# CrabTimerMain.net
KiCad netlist of a schematic drawn in EAGLE
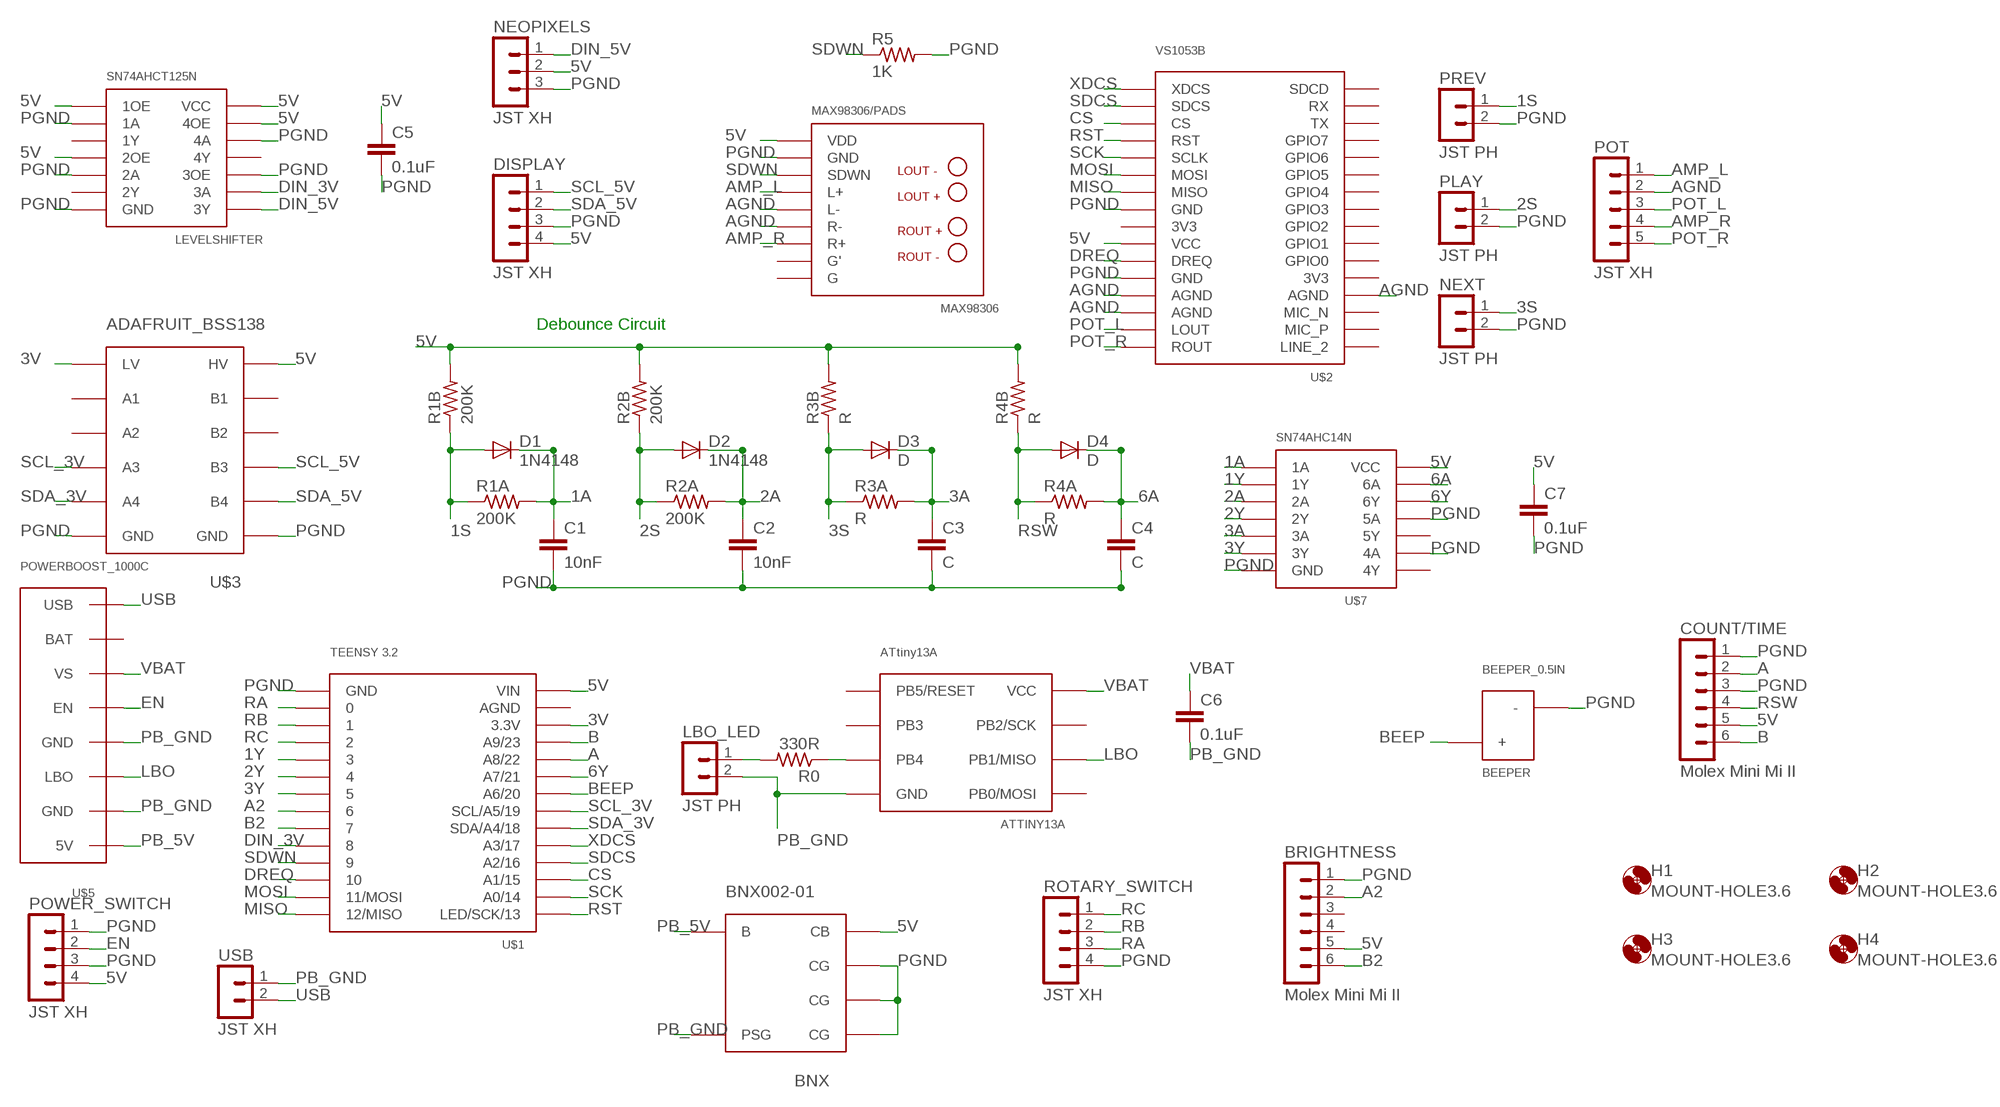
[diagram p0: schematic, sheet 1]

(export (version "E")
  (design (tool "Eeschema 10.0.6"))
  (components
    (comp (ref "ATTINY13A")
      (value "ATtiny13A")
      (footprint "eagle-import:ATTINY13A")
      (libsource (lib "eagle-import") (part "ATTINY13A"))
    )
    (comp (ref "BEEPER")
      (value "BEEPER_0.5IN")
      (footprint "eagle-import:BEEPER_0.5IN")
      (libsource (lib "eagle-import") (part "BEEPER_0.5IN"))
    )
    (comp (ref "BNX002-01")
      (value "BNX")
      (footprint "eagle-import:BNX002-01")
      (libsource (lib "eagle-import") (part "BNX"))
    )
    (comp (ref "BRIGHTNESS")
      (value "Molex Mini Mi II")
      (footprint "eagle-import:55447-0670")
      (libsource (lib "eagle-import") (part "MOLEX-55447-0670LONG_PADS"))
    )
    (comp (ref "C1")
      (value "10nF")
      (footprint "eagle-import:CAPACITOR_0.1IN")
      (libsource (lib "eagle-import") (part "CAPACITORS0.1IN"))
    )
    (comp (ref "C2")
      (value "10nF")
      (footprint "eagle-import:CAPACITOR_0.1IN")
      (libsource (lib "eagle-import") (part "CAPACITORS0.1IN"))
    )
    (comp (ref "C3")
      (value "C")
      (footprint "eagle-import:CAPACITOR_0.1IN")
      (libsource (lib "eagle-import") (part "CAPACITORS0.1IN"))
    )
    (comp (ref "C4")
      (value "C")
      (footprint "eagle-import:CAPACITOR_0.1IN")
      (libsource (lib "eagle-import") (part "CAPACITORS0.1IN"))
    )
    (comp (ref "C5")
      (value "0.1uF")
      (footprint "eagle-import:CAPACITOR_0.1IN")
      (libsource (lib "eagle-import") (part "CAPACITORS0.1IN"))
    )
    (comp (ref "C6")
      (value "0.1uF")
      (footprint "eagle-import:CAPACITOR_0.1IN")
      (libsource (lib "eagle-import") (part "CAPACITORS0.1IN"))
    )
    (comp (ref "C7")
      (value "0.1uF")
      (footprint "eagle-import:CAPACITOR_0.1IN")
      (libsource (lib "eagle-import") (part "CAPACITORS0.1IN"))
    )
    (comp (ref "COUNT/TIME")
      (value "Molex Mini Mi II")
      (footprint "eagle-import:55454-0670")
      (libsource (lib "eagle-import") (part "MOLEX-55454-0670LONGPADS"))
    )
    (comp (ref "D1")
      (value "1N4148")
      (footprint "eagle-import:1N4148")
      (libsource (lib "eagle-import") (part "1N4148"))
    )
    (comp (ref "D2")
      (value "1N4148")
      (footprint "eagle-import:1N4148")
      (libsource (lib "eagle-import") (part "1N4148"))
    )
    (comp (ref "D3")
      (value "D")
      (footprint "eagle-import:1N4148")
      (libsource (lib "eagle-import") (part "1N4148"))
    )
    (comp (ref "D4")
      (value "D")
      (footprint "eagle-import:1N4148")
      (libsource (lib "eagle-import") (part "1N4148"))
    )
    (comp (ref "DISPLAY")
      (value "JST XH")
      (footprint "eagle-import:B4B-XH-A")
      (libsource (lib "eagle-import") (part "JST-B4B-XH-A"))
    )
    (comp (ref "H1")
      (value "MOUNT-HOLE3.6")
      (footprint "eagle-import:3,6")
      (libsource (lib "eagle-import") (part "MOUNT-HOLE3.6"))
    )
    (comp (ref "H2")
      (value "MOUNT-HOLE3.6")
      (footprint "eagle-import:3,6")
      (libsource (lib "eagle-import") (part "MOUNT-HOLE3.6"))
    )
    (comp (ref "H3")
      (value "MOUNT-HOLE3.6")
      (footprint "eagle-import:3,6")
      (libsource (lib "eagle-import") (part "MOUNT-HOLE3.6"))
    )
    (comp (ref "H4")
      (value "MOUNT-HOLE3.6")
      (footprint "eagle-import:3,6")
      (libsource (lib "eagle-import") (part "MOUNT-HOLE3.6"))
    )
    (comp (ref "LBO_LED")
      (value "JST PH")
      (footprint "eagle-import:B2B-PH-K-S")
      (libsource (lib "eagle-import") (part "JST-B2B-PH-K-S"))
    )
    (comp (ref "LEVELSHIFTER")
      (value "SN74AHCT125N")
      (footprint "eagle-import:SN74AHCT125N")
      (libsource (lib "eagle-import") (part "SN74AHCT125N"))
    )
    (comp (ref "MAX98306")
      (value "MAX98306/PADS")
      (footprint "eagle-import:MAX98306")
      (libsource (lib "eagle-import") (part "MAX98306/PADS"))
    )
    (comp (ref "NEOPIXELS")
      (value "JST XH")
      (footprint "eagle-import:B3B-XH-A")
      (libsource (lib "eagle-import") (part "JST-B3B-XH-A"))
    )
    (comp (ref "NEXT")
      (value "JST PH")
      (footprint "eagle-import:B2B-PH-K-S")
      (libsource (lib "eagle-import") (part "JST-B2B-PH-K-S"))
    )
    (comp (ref "PLAY")
      (value "JST PH")
      (footprint "eagle-import:B2B-PH-K-S")
      (libsource (lib "eagle-import") (part "JST-B2B-PH-K-S"))
    )
    (comp (ref "POT")
      (value "JST XH")
      (footprint "eagle-import:B5B-XH-A")
      (libsource (lib "eagle-import") (part "JST-B5B-XH-A"))
    )
    (comp (ref "POWER_SWITCH")
      (value "JST XH")
      (footprint "eagle-import:B4B-XH-A")
      (libsource (lib "eagle-import") (part "JST-B4B-XH-A"))
    )
    (comp (ref "PREV")
      (value "JST PH")
      (footprint "eagle-import:B2B-PH-K-S")
      (libsource (lib "eagle-import") (part "JST-B2B-PH-K-S"))
    )
    (comp (ref "R0")
      (value "330R")
      (footprint "eagle-import:RESISTOR_0.15IN")
      (libsource (lib "eagle-import") (part "RESISTORS0.15IN"))
    )
    (comp (ref "R1A")
      (value "200K")
      (footprint "eagle-import:RESISTOR_0.15IN")
      (libsource (lib "eagle-import") (part "RESISTORS0.15IN"))
    )
    (comp (ref "R1B")
      (value "200K")
      (footprint "eagle-import:RESISTOR_0.15IN")
      (libsource (lib "eagle-import") (part "RESISTORS0.15IN"))
    )
    (comp (ref "R2A")
      (value "200K")
      (footprint "eagle-import:RESISTOR_0.15IN")
      (libsource (lib "eagle-import") (part "RESISTORS0.15IN"))
    )
    (comp (ref "R2B")
      (value "200K")
      (footprint "eagle-import:RESISTOR_0.15IN")
      (libsource (lib "eagle-import") (part "RESISTORS0.15IN"))
    )
    (comp (ref "R3A")
      (value "R")
      (footprint "eagle-import:RESISTOR_0.15IN")
      (libsource (lib "eagle-import") (part "RESISTORS0.15IN"))
    )
    (comp (ref "R3B")
      (value "R")
      (footprint "eagle-import:RESISTOR_0.15IN")
      (libsource (lib "eagle-import") (part "RESISTORS0.15IN"))
    )
    (comp (ref "R4A")
      (value "R")
      (footprint "eagle-import:RESISTOR_0.15IN")
      (libsource (lib "eagle-import") (part "RESISTORS0.15IN"))
    )
    (comp (ref "R4B")
      (value "R")
      (footprint "eagle-import:RESISTOR_0.15IN")
      (libsource (lib "eagle-import") (part "RESISTORS0.15IN"))
    )
    (comp (ref "R5")
      (value "1K")
      (footprint "eagle-import:RESISTOR_0.15IN")
      (libsource (lib "eagle-import") (part "RESISTORS0.15IN"))
    )
    (comp (ref "ROTARY_SWITCH")
      (value "JST XH")
      (footprint "eagle-import:B4B-XH-A")
      (libsource (lib "eagle-import") (part "JST-B4B-XH-A"))
    )
    (comp (ref "U$1")
      (value "TEENSY 3.2")
      (footprint "eagle-import:TEENSY-3.1")
      (libsource (lib "eagle-import") (part "TEENSY-3.1"))
    )
    (comp (ref "U$2")
      (value "VS1053B")
      (footprint "eagle-import:VS1053B")
      (libsource (lib "eagle-import") (part "VS1053B"))
    )
    (comp (ref "U$3")
      (value "ADAFRUIT_BSS138")
      (footprint "eagle-import:ADAFRUIT_BSS138")
      (libsource (lib "eagle-import") (part "ADAFRUIT_BSS138"))
    )
    (comp (ref "U$5")
      (value "POWERBOOST_1000C")
      (footprint "eagle-import:POWERBOOST_1000C")
      (libsource (lib "eagle-import") (part "POWERBOOST_1000C"))
    )
    (comp (ref "U$7")
      (value "SN74AHC14N")
      (footprint "eagle-import:SN74AHC14N")
      (libsource (lib "eagle-import") (part "SN74AHC14N"))
    )
    (comp (ref "USB")
      (value "JST XH")
      (footprint "eagle-import:B2B-XH-A")
      (libsource (lib "eagle-import") (part "JST-B2B-XH-A"))
    )
  )
  (nets
    (net (code "1") (name "/1A") (class "Default")
      (node (ref "C1") (pin "P$1") (pinfunction "1_P$1") (pintype "passive"))
      (node (ref "D1") (pin "C") (pinfunction "C_C") (pintype "passive"))
      (node (ref "R1A") (pin "2") (pinfunction "2_2") (pintype "passive"))
      (node (ref "U$7") (pin "1A") (pinfunction "1A_1A") (pintype "input"))
    )
    (net (code "2") (name "/1S") (class "Default")
      (node (ref "D1") (pin "A") (pinfunction "A_A") (pintype "passive"))
      (node (ref "PREV") (pin "1") (pinfunction "1_1") (pintype "passive"))
      (node (ref "R1A") (pin "1") (pinfunction "1_1") (pintype "passive"))
      (node (ref "R1B") (pin "1") (pinfunction "1_1") (pintype "passive"))
    )
    (net (code "3") (name "/1Y") (class "Default")
      (node (ref "U$1") (pin "3") (pinfunction "3_3") (pintype "bidirectional"))
      (node (ref "U$7") (pin "1Y") (pinfunction "1Y_1Y") (pintype "output"))
    )
    (net (code "4") (name "/2A") (class "Default")
      (node (ref "C2") (pin "P$1") (pinfunction "1_P$1") (pintype "passive"))
      (node (ref "D2") (pin "C") (pinfunction "C_C") (pintype "passive"))
      (node (ref "R2A") (pin "2") (pinfunction "2_2") (pintype "passive"))
      (node (ref "U$7") (pin "2A") (pinfunction "2A_2A") (pintype "input"))
    )
    (net (code "5") (name "/2S") (class "Default")
      (node (ref "D2") (pin "A") (pinfunction "A_A") (pintype "passive"))
      (node (ref "PLAY") (pin "1") (pinfunction "1_1") (pintype "passive"))
      (node (ref "R2A") (pin "1") (pinfunction "1_1") (pintype "passive"))
      (node (ref "R2B") (pin "1") (pinfunction "1_1") (pintype "passive"))
    )
    (net (code "6") (name "/2Y") (class "Default")
      (node (ref "U$1") (pin "4") (pinfunction "4_4") (pintype "bidirectional"))
      (node (ref "U$7") (pin "2Y") (pinfunction "2Y_2Y") (pintype "output"))
    )
    (net (code "7") (name "/3A") (class "Default")
      (node (ref "C3") (pin "P$1") (pinfunction "1_P$1") (pintype "passive"))
      (node (ref "D3") (pin "C") (pinfunction "C_C") (pintype "passive"))
      (node (ref "R3A") (pin "2") (pinfunction "2_2") (pintype "passive"))
      (node (ref "U$7") (pin "3A") (pinfunction "3A_3A") (pintype "input"))
    )
    (net (code "8") (name "/3S") (class "Default")
      (node (ref "D3") (pin "A") (pinfunction "A_A") (pintype "passive"))
      (node (ref "NEXT") (pin "1") (pinfunction "1_1") (pintype "passive"))
      (node (ref "R3A") (pin "1") (pinfunction "1_1") (pintype "passive"))
      (node (ref "R3B") (pin "1") (pinfunction "1_1") (pintype "passive"))
    )
    (net (code "9") (name "/3V") (class "Default")
      (node (ref "U$1") (pin "3.3V") (pinfunction "3.3V_3.3V") (pintype "bidirectional"))
      (node (ref "U$3") (pin "LV") (pinfunction "LV_LV") (pintype "power_in"))
    )
    (net (code "10") (name "/3Y") (class "Default")
      (node (ref "U$1") (pin "5") (pinfunction "5_5") (pintype "bidirectional"))
      (node (ref "U$7") (pin "3Y") (pinfunction "3Y_3Y") (pintype "output"))
    )
    (net (code "11") (name "/5V") (class "Default")
      (node (ref "BNX002-01") (pin "CB") (pinfunction "CB_CB") (pintype "power_in"))
      (node (ref "BRIGHTNESS") (pin "5") (pinfunction "5_5") (pintype "passive"))
      (node (ref "C5") (pin "P$1") (pinfunction "1_P$1") (pintype "passive"))
      (node (ref "C7") (pin "P$1") (pinfunction "1_P$1") (pintype "passive"))
      (node (ref "COUNT/TIME") (pin "5") (pinfunction "5_5") (pintype "passive"))
      (node (ref "DISPLAY") (pin "4") (pinfunction "4_4") (pintype "passive"))
      (node (ref "LEVELSHIFTER") (pin "1OE") (pinfunction "1OE_1OE") (pintype "input"))
      (node (ref "LEVELSHIFTER") (pin "2OE") (pinfunction "2OE_2OE") (pintype "output"))
      (node (ref "LEVELSHIFTER") (pin "4OE") (pinfunction "4OE_4OE") (pintype "input"))
      (node (ref "LEVELSHIFTER") (pin "VCC@1") (pinfunction "VCC_VCC@1") (pintype "power_in"))
      (node (ref "MAX98306") (pin "VDD@1") (pinfunction "VDD_VDD@1") (pintype "power_in"))
      (node (ref "NEOPIXELS") (pin "2") (pinfunction "2_2") (pintype "passive"))
      (node (ref "POWER_SWITCH") (pin "4") (pinfunction "4_4") (pintype "passive"))
      (node (ref "R1B") (pin "2") (pinfunction "2_2") (pintype "passive"))
      (node (ref "R2B") (pin "2") (pinfunction "2_2") (pintype "passive"))
      (node (ref "R3B") (pin "2") (pinfunction "2_2") (pintype "passive"))
      (node (ref "R4B") (pin "2") (pinfunction "2_2") (pintype "passive"))
      (node (ref "U$1") (pin "VIN") (pinfunction "VIN_VIN") (pintype "power_in"))
      (node (ref "U$2") (pin "VCC") (pinfunction "VCC_VCC") (pintype "power_in"))
      (node (ref "U$3") (pin "HV") (pinfunction "HV_HV") (pintype "power_in"))
      (node (ref "U$7") (pin "VCC@1") (pinfunction "VCC_VCC@1") (pintype "power_in"))
    )
    (net (code "12") (name "/6A") (class "Default")
      (node (ref "C4") (pin "P$1") (pinfunction "1_P$1") (pintype "passive"))
      (node (ref "D4") (pin "C") (pinfunction "C_C") (pintype "passive"))
      (node (ref "R4A") (pin "2") (pinfunction "2_2") (pintype "passive"))
      (node (ref "U$7") (pin "6A") (pinfunction "6A_6A") (pintype "input"))
    )
    (net (code "13") (name "/6Y") (class "Default")
      (node (ref "U$1") (pin "A7/21") (pinfunction "A7/21_A7/21") (pintype "bidirectional"))
      (node (ref "U$7") (pin "6Y") (pinfunction "6Y_6Y") (pintype "output"))
    )
    (net (code "14") (name "/A") (class "Default")
      (node (ref "COUNT/TIME") (pin "2") (pinfunction "2_2") (pintype "passive"))
      (node (ref "U$1") (pin "A8/22") (pinfunction "A8/22_A8/22") (pintype "bidirectional"))
    )
    (net (code "15") (name "/A2") (class "Default")
      (node (ref "BRIGHTNESS") (pin "2") (pinfunction "2_2") (pintype "passive"))
      (node (ref "U$1") (pin "6") (pinfunction "6_6") (pintype "bidirectional"))
    )
    (net (code "16") (name "/AGND") (class "Default")
      (node (ref "MAX98306") (pin "L-") (pinfunction "L-_L-") (pintype "input"))
      (node (ref "MAX98306") (pin "R-") (pinfunction "R-_R-") (pintype "input"))
      (node (ref "POT") (pin "2") (pinfunction "2_2") (pintype "passive"))
      (node (ref "U$2") (pin "AGND@1") (pinfunction "AGND_AGND@1") (pintype "power_in"))
      (node (ref "U$2") (pin "AGND@2") (pinfunction "AGND_AGND@2") (pintype "power_in"))
      (node (ref "U$2") (pin "AGND@3") (pinfunction "AGND_AGND@3") (pintype "power_in"))
    )
    (net (code "17") (name "/AMP_L") (class "Default")
      (node (ref "MAX98306") (pin "L+") (pinfunction "L+_L+") (pintype "input"))
      (node (ref "POT") (pin "1") (pinfunction "1_1") (pintype "passive"))
    )
    (net (code "18") (name "/AMP_R") (class "Default")
      (node (ref "MAX98306") (pin "R+") (pinfunction "R+_R+") (pintype "input"))
      (node (ref "POT") (pin "4") (pinfunction "4_4") (pintype "passive"))
    )
    (net (code "19") (name "/B") (class "Default")
      (node (ref "COUNT/TIME") (pin "6") (pinfunction "6_6") (pintype "passive"))
      (node (ref "U$1") (pin "A9/23") (pinfunction "A9/23_A9/23") (pintype "bidirectional"))
    )
    (net (code "20") (name "/B2") (class "Default")
      (node (ref "BRIGHTNESS") (pin "6") (pinfunction "6_6") (pintype "passive"))
      (node (ref "U$1") (pin "7") (pinfunction "7_7") (pintype "bidirectional"))
    )
    (net (code "21") (name "/BEEP") (class "Default")
      (node (ref "BEEPER") (pin "+") (pinfunction "+_+") (pintype "passive"))
      (node (ref "U$1") (pin "A6/20") (pinfunction "A6/20_A6/20") (pintype "bidirectional"))
    )
    (net (code "22") (name "/CS") (class "Default")
      (node (ref "U$1") (pin "A1/15") (pinfunction "A1/15_A1/15") (pintype "bidirectional"))
      (node (ref "U$2") (pin "CS") (pinfunction "CS_CS") (pintype "input"))
    )
    (net (code "23") (name "/DIN_3V") (class "Default")
      (node (ref "LEVELSHIFTER") (pin "3A") (pinfunction "3A_3A") (pintype "input"))
      (node (ref "U$1") (pin "8") (pinfunction "8_8") (pintype "bidirectional"))
    )
    (net (code "24") (name "/DIN_5V") (class "Default")
      (node (ref "LEVELSHIFTER") (pin "3Y") (pinfunction "3Y_3Y") (pintype "output"))
      (node (ref "NEOPIXELS") (pin "1") (pinfunction "1_1") (pintype "passive"))
    )
    (net (code "25") (name "/DREQ") (class "Default")
      (node (ref "U$1") (pin "10") (pinfunction "10_10") (pintype "bidirectional"))
      (node (ref "U$2") (pin "DREQ") (pinfunction "DREQ_DREQ") (pintype "output"))
    )
    (net (code "26") (name "/EN") (class "Default")
      (node (ref "POWER_SWITCH") (pin "2") (pinfunction "2_2") (pintype "passive"))
      (node (ref "U$5") (pin "P$EN") (pinfunction "EN_P$EN") (pintype "bidirectional"))
    )
    (net (code "27") (name "/LBO") (class "Default")
      (node (ref "ATTINY13A") (pin "PB1/MISO") (pinfunction "PB1/MISO_PB1/MISO") (pintype "bidirectional"))
      (node (ref "U$5") (pin "P$LBO") (pinfunction "LBO_P$LBO") (pintype "bidirectional"))
    )
    (net (code "28") (name "/MISO") (class "Default")
      (node (ref "U$1") (pin "12/MISO") (pinfunction "12/MISO_12/MISO") (pintype "bidirectional"))
      (node (ref "U$2") (pin "MISO") (pinfunction "MISO_MISO") (pintype "output"))
    )
    (net (code "29") (name "/MOSI") (class "Default")
      (node (ref "U$1") (pin "11/MOSI") (pinfunction "11/MOSI_11/MOSI") (pintype "bidirectional"))
      (node (ref "U$2") (pin "MOSI") (pinfunction "MOSI_MOSI") (pintype "input"))
    )
    (net (code "30") (name "/PB_5V") (class "Default")
      (node (ref "BNX002-01") (pin "B") (pinfunction "B_B") (pintype "power_in"))
      (node (ref "U$5") (pin "P$5V") (pinfunction "5V_P$5V") (pintype "power_in"))
    )
    (net (code "31") (name "/PB_GND") (class "Default")
      (node (ref "ATTINY13A") (pin "GND") (pinfunction "GND_GND") (pintype "power_in"))
      (node (ref "BNX002-01") (pin "PSG") (pinfunction "PSG_PSG") (pintype "power_in"))
      (node (ref "C6") (pin "P$2") (pinfunction "2_P$2") (pintype "passive"))
      (node (ref "LBO_LED") (pin "2") (pinfunction "2_2") (pintype "passive"))
      (node (ref "U$5") (pin "P$GND@1") (pinfunction "GND_P$GND@1") (pintype "power_in"))
      (node (ref "U$5") (pin "P$GND@2") (pinfunction "GND_P$GND@2") (pintype "power_in"))
      (node (ref "USB") (pin "1") (pinfunction "1_1") (pintype "passive"))
    )
    (net (code "32") (name "/PGND") (class "Default")
      (node (ref "BEEPER") (pin "-") (pinfunction "-_-") (pintype "passive"))
      (node (ref "BNX002-01") (pin "CG@1") (pinfunction "CG_CG@1") (pintype "power_in"))
      (node (ref "BNX002-01") (pin "CG@2") (pinfunction "CG_CG@2") (pintype "power_in"))
      (node (ref "BNX002-01") (pin "CG@3") (pinfunction "CG_CG@3") (pintype "power_in"))
      (node (ref "BRIGHTNESS") (pin "1") (pinfunction "1_1") (pintype "passive"))
      (node (ref "C1") (pin "P$2") (pinfunction "2_P$2") (pintype "passive"))
      (node (ref "C2") (pin "P$2") (pinfunction "2_P$2") (pintype "passive"))
      (node (ref "C3") (pin "P$2") (pinfunction "2_P$2") (pintype "passive"))
      (node (ref "C4") (pin "P$2") (pinfunction "2_P$2") (pintype "passive"))
      (node (ref "C5") (pin "P$2") (pinfunction "2_P$2") (pintype "passive"))
      (node (ref "C7") (pin "P$2") (pinfunction "2_P$2") (pintype "passive"))
      (node (ref "COUNT/TIME") (pin "1") (pinfunction "1_1") (pintype "passive"))
      (node (ref "COUNT/TIME") (pin "3") (pinfunction "3_3") (pintype "passive"))
      (node (ref "DISPLAY") (pin "3") (pinfunction "3_3") (pintype "passive"))
      (node (ref "LEVELSHIFTER") (pin "1A") (pinfunction "1A_1A") (pintype "output"))
      (node (ref "LEVELSHIFTER") (pin "2A") (pinfunction "2A_2A") (pintype "input"))
      (node (ref "LEVELSHIFTER") (pin "3OE") (pinfunction "3OE_3OE") (pintype "output"))
      (node (ref "LEVELSHIFTER") (pin "4A") (pinfunction "4A_4A") (pintype "output"))
      (node (ref "LEVELSHIFTER") (pin "GND@1") (pinfunction "GND_GND@1") (pintype "power_in"))
      (node (ref "MAX98306") (pin "GND@1") (pinfunction "GND_GND@1") (pintype "power_in"))
      (node (ref "NEOPIXELS") (pin "3") (pinfunction "3_3") (pintype "passive"))
      (node (ref "NEXT") (pin "2") (pinfunction "2_2") (pintype "passive"))
      (node (ref "PLAY") (pin "2") (pinfunction "2_2") (pintype "passive"))
      (node (ref "POWER_SWITCH") (pin "1") (pinfunction "1_1") (pintype "passive"))
      (node (ref "POWER_SWITCH") (pin "3") (pinfunction "3_3") (pintype "passive"))
      (node (ref "PREV") (pin "2") (pinfunction "2_2") (pintype "passive"))
      (node (ref "R5") (pin "2") (pinfunction "2_2") (pintype "passive"))
      (node (ref "ROTARY_SWITCH") (pin "4") (pinfunction "4_4") (pintype "passive"))
      (node (ref "U$1") (pin "GND") (pinfunction "GND_GND") (pintype "power_in"))
      (node (ref "U$2") (pin "GND@1") (pinfunction "GND_GND@1") (pintype "power_in"))
      (node (ref "U$2") (pin "GND@2") (pinfunction "GND_GND@2") (pintype "power_in"))
      (node (ref "U$3") (pin "GND@1") (pinfunction "GND_GND@1") (pintype "power_in"))
      (node (ref "U$3") (pin "GND@2") (pinfunction "GND_GND@2") (pintype "bidirectional"))
      (node (ref "U$7") (pin "4A") (pinfunction "4A_4A") (pintype "input"))
      (node (ref "U$7") (pin "5A") (pinfunction "5A_5A") (pintype "input"))
      (node (ref "U$7") (pin "GND@1") (pinfunction "GND_GND@1") (pintype "power_in"))
    )
    (net (code "33") (name "/POT_L") (class "Default")
      (node (ref "POT") (pin "3") (pinfunction "3_3") (pintype "passive"))
      (node (ref "U$2") (pin "LOUT") (pinfunction "LOUT_LOUT") (pintype "output"))
    )
    (net (code "34") (name "/POT_R") (class "Default")
      (node (ref "POT") (pin "5") (pinfunction "5_5") (pintype "passive"))
      (node (ref "U$2") (pin "ROUT") (pinfunction "ROUT_ROUT") (pintype "output"))
    )
    (net (code "35") (name "/RA") (class "Default")
      (node (ref "ROTARY_SWITCH") (pin "3") (pinfunction "3_3") (pintype "passive"))
      (node (ref "U$1") (pin "0") (pinfunction "0_0") (pintype "bidirectional"))
    )
    (net (code "36") (name "/RB") (class "Default")
      (node (ref "ROTARY_SWITCH") (pin "2") (pinfunction "2_2") (pintype "passive"))
      (node (ref "U$1") (pin "1") (pinfunction "1_1") (pintype "bidirectional"))
    )
    (net (code "37") (name "/RC") (class "Default")
      (node (ref "ROTARY_SWITCH") (pin "1") (pinfunction "1_1") (pintype "passive"))
      (node (ref "U$1") (pin "2") (pinfunction "2_2") (pintype "bidirectional"))
    )
    (net (code "38") (name "/RST") (class "Default")
      (node (ref "U$1") (pin "LED/SCK/13") (pinfunction "LED/SCK/13_LED/SCK/13") (pintype "bidirectional"))
      (node (ref "U$2") (pin "RST") (pinfunction "RST_RST") (pintype "input"))
    )
    (net (code "39") (name "/RSW") (class "Default")
      (node (ref "COUNT/TIME") (pin "4") (pinfunction "4_4") (pintype "passive"))
      (node (ref "D4") (pin "A") (pinfunction "A_A") (pintype "passive"))
      (node (ref "R4A") (pin "1") (pinfunction "1_1") (pintype "passive"))
      (node (ref "R4B") (pin "1") (pinfunction "1_1") (pintype "passive"))
    )
    (net (code "40") (name "/SCK") (class "Default")
      (node (ref "U$1") (pin "A0/14") (pinfunction "A0/14_A0/14") (pintype "bidirectional"))
      (node (ref "U$2") (pin "SCLK") (pinfunction "SCLK_SCLK") (pintype "input"))
    )
    (net (code "41") (name "/SCL_3V") (class "Default")
      (node (ref "U$1") (pin "SCL/A5/19") (pinfunction "SCL/A5/19_SCL/A5/19") (pintype "bidirectional"))
      (node (ref "U$3") (pin "A3") (pinfunction "A3_A3") (pintype "bidirectional"))
    )
    (net (code "42") (name "/SCL_5V") (class "Default")
      (node (ref "DISPLAY") (pin "1") (pinfunction "1_1") (pintype "passive"))
      (node (ref "U$3") (pin "B3") (pinfunction "B3_B3") (pintype "bidirectional"))
    )
    (net (code "43") (name "/SDA_3V") (class "Default")
      (node (ref "U$1") (pin "SDA/A4/18") (pinfunction "SDA/A4/18_SDA/A4/18") (pintype "bidirectional"))
      (node (ref "U$3") (pin "A4") (pinfunction "A4_A4") (pintype "bidirectional"))
    )
    (net (code "44") (name "/SDA_5V") (class "Default")
      (node (ref "DISPLAY") (pin "2") (pinfunction "2_2") (pintype "passive"))
      (node (ref "U$3") (pin "B4") (pinfunction "B4_B4") (pintype "bidirectional"))
    )
    (net (code "45") (name "/SDCS") (class "Default")
      (node (ref "U$1") (pin "A2/16") (pinfunction "A2/16_A2/16") (pintype "bidirectional"))
      (node (ref "U$2") (pin "SDCS") (pinfunction "SDCS_SDCS") (pintype "input"))
    )
    (net (code "46") (name "/SDWN") (class "Default")
      (node (ref "MAX98306") (pin "SDWN") (pinfunction "SDWN_SDWN") (pintype "input"))
      (node (ref "R5") (pin "1") (pinfunction "1_1") (pintype "passive"))
      (node (ref "U$1") (pin "9") (pinfunction "9_9") (pintype "bidirectional"))
    )
    (net (code "47") (name "/USB") (class "Default")
      (node (ref "U$5") (pin "P$USB") (pinfunction "USB_P$USB") (pintype "bidirectional"))
      (node (ref "USB") (pin "2") (pinfunction "2_2") (pintype "passive"))
    )
    (net (code "48") (name "/VBAT") (class "Default")
      (node (ref "ATTINY13A") (pin "VCC") (pinfunction "VCC_VCC") (pintype "power_in"))
      (node (ref "C6") (pin "P$1") (pinfunction "1_P$1") (pintype "passive"))
      (node (ref "U$5") (pin "P$VS") (pinfunction "VS_P$VS") (pintype "bidirectional"))
    )
    (net (code "49") (name "/XDCS") (class "Default")
      (node (ref "U$1") (pin "A3/17") (pinfunction "A3/17_A3/17") (pintype "bidirectional"))
      (node (ref "U$2") (pin "XDCS") (pinfunction "XDCS_XDCS") (pintype "input"))
    )
    (net (code "50") (name "Net-(ATTINY13A-PadPB4)") (class "Default")
      (node (ref "ATTINY13A") (pin "PB4") (pinfunction "PB4_PB4") (pintype "bidirectional"))
      (node (ref "R0") (pin "1") (pinfunction "1_1") (pintype "passive"))
    )
    (net (code "51") (name "Net-(LBO_LED-Pad1)") (class "Default")
      (node (ref "LBO_LED") (pin "1") (pinfunction "1_1") (pintype "passive"))
      (node (ref "R0") (pin "2") (pinfunction "2_2") (pintype "passive"))
    )
    (net (code "52") (name "unconnected-(ATTINY13A-PadPB0{slash}MOSI)") (class "Default")
      (node (ref "ATTINY13A") (pin "PB0/MOSI") (pinfunction "PB0/MOSI_PB0/MOSI") (pintype "bidirectional"))
    )
    (net (code "53") (name "unconnected-(ATTINY13A-PadPB2{slash}SCK)") (class "Default")
      (node (ref "ATTINY13A") (pin "PB2/SCK") (pinfunction "PB2/SCK_PB2/SCK") (pintype "bidirectional"))
    )
    (net (code "54") (name "unconnected-(ATTINY13A-PadPB3)") (class "Default")
      (node (ref "ATTINY13A") (pin "PB3") (pinfunction "PB3_PB3") (pintype "bidirectional"))
    )
    (net (code "55") (name "unconnected-(ATTINY13A-PadPB5{slash}RESET)") (class "Default")
      (node (ref "ATTINY13A") (pin "PB5/RESET") (pinfunction "PB5/RESET_PB5/RESET") (pintype "bidirectional"))
    )
    (net (code "56") (name "unconnected-(BRIGHTNESS-Pad3)") (class "Default")
      (node (ref "BRIGHTNESS") (pin "3") (pinfunction "3_3") (pintype "passive"))
    )
    (net (code "57") (name "unconnected-(BRIGHTNESS-Pad4)") (class "Default")
      (node (ref "BRIGHTNESS") (pin "4") (pinfunction "4_4") (pintype "passive"))
    )
    (net (code "58") (name "unconnected-(LEVELSHIFTER-Pad1Y)") (class "Default")
      (node (ref "LEVELSHIFTER") (pin "1Y") (pinfunction "1Y_1Y") (pintype "input"))
    )
    (net (code "59") (name "unconnected-(LEVELSHIFTER-Pad2Y)") (class "Default")
      (node (ref "LEVELSHIFTER") (pin "2Y") (pinfunction "2Y_2Y") (pintype "output"))
    )
    (net (code "60") (name "unconnected-(LEVELSHIFTER-Pad4Y)") (class "Default")
      (node (ref "LEVELSHIFTER") (pin "4Y") (pinfunction "4Y_4Y") (pintype "input"))
    )
    (net (code "61") (name "unconnected-(MAX98306-PadG')") (class "Default")
      (node (ref "MAX98306") (pin "G'") (pinfunction "G'_G'") (pintype "bidirectional"))
    )
    (net (code "62") (name "unconnected-(MAX98306-PadG)") (class "Default")
      (node (ref "MAX98306") (pin "G") (pinfunction "G_G") (pintype "bidirectional"))
    )
    (net (code "63") (name "unconnected-(U$1-PadAGND)") (class "Default")
      (node (ref "U$1") (pin "AGND") (pinfunction "AGND_AGND") (pintype "bidirectional"))
    )
    (net (code "64") (name "unconnected-(U$2-3V3-Pad3V3@1)") (class "Default")
      (node (ref "U$2") (pin "3V3@1") (pinfunction "3V3_3V3@1") (pintype "output"))
    )
    (net (code "65") (name "unconnected-(U$2-3V3-Pad3V3@2)") (class "Default")
      (node (ref "U$2") (pin "3V3@2") (pinfunction "3V3_3V3@2") (pintype "output"))
    )
    (net (code "66") (name "unconnected-(U$2-PadGPIO0)") (class "Default")
      (node (ref "U$2") (pin "GPIO0") (pinfunction "GPIO0_GPIO0") (pintype "bidirectional"))
    )
    (net (code "67") (name "unconnected-(U$2-PadGPIO1)") (class "Default")
      (node (ref "U$2") (pin "GPIO1") (pinfunction "GPIO1_GPIO1") (pintype "bidirectional"))
    )
    (net (code "68") (name "unconnected-(U$2-PadGPIO2)") (class "Default")
      (node (ref "U$2") (pin "GPIO2") (pinfunction "GPIO2_GPIO2") (pintype "bidirectional"))
    )
    (net (code "69") (name "unconnected-(U$2-PadGPIO3)") (class "Default")
      (node (ref "U$2") (pin "GPIO3") (pinfunction "GPIO3_GPIO3") (pintype "bidirectional"))
    )
    (net (code "70") (name "unconnected-(U$2-PadGPIO4)") (class "Default")
      (node (ref "U$2") (pin "GPIO4") (pinfunction "GPIO4_GPIO4") (pintype "bidirectional"))
    )
    (net (code "71") (name "unconnected-(U$2-PadGPIO5)") (class "Default")
      (node (ref "U$2") (pin "GPIO5") (pinfunction "GPIO5_GPIO5") (pintype "bidirectional"))
    )
    (net (code "72") (name "unconnected-(U$2-PadGPIO6)") (class "Default")
      (node (ref "U$2") (pin "GPIO6") (pinfunction "GPIO6_GPIO6") (pintype "bidirectional"))
    )
    (net (code "73") (name "unconnected-(U$2-PadGPIO7)") (class "Default")
      (node (ref "U$2") (pin "GPIO7") (pinfunction "GPIO7_GPIO7") (pintype "bidirectional"))
    )
    (net (code "74") (name "unconnected-(U$2-PadLINE_2)") (class "Default")
      (node (ref "U$2") (pin "LINE_2") (pinfunction "LINE_2_LINE_2") (pintype "output"))
    )
    (net (code "75") (name "unconnected-(U$2-PadMIC_N)") (class "Default")
      (node (ref "U$2") (pin "MIC_N") (pinfunction "MIC_N_MIC_N") (pintype "input"))
    )
    (net (code "76") (name "unconnected-(U$2-PadMIC_P)") (class "Default")
      (node (ref "U$2") (pin "MIC_P") (pinfunction "MIC_P_MIC_P") (pintype "input"))
    )
    (net (code "77") (name "unconnected-(U$2-PadRX)") (class "Default")
      (node (ref "U$2") (pin "RX") (pinfunction "RX_RX") (pintype "input"))
    )
    (net (code "78") (name "unconnected-(U$2-PadSDCD)") (class "Default")
      (node (ref "U$2") (pin "SDCD") (pinfunction "SDCD_SDCD") (pintype "bidirectional"))
    )
    (net (code "79") (name "unconnected-(U$2-PadTX)") (class "Default")
      (node (ref "U$2") (pin "TX") (pinfunction "TX_TX") (pintype "output"))
    )
    (net (code "80") (name "unconnected-(U$3-PadA1)") (class "Default")
      (node (ref "U$3") (pin "A1") (pinfunction "A1_A1") (pintype "bidirectional"))
    )
    (net (code "81") (name "unconnected-(U$3-PadA2)") (class "Default")
      (node (ref "U$3") (pin "A2") (pinfunction "A2_A2") (pintype "bidirectional"))
    )
    (net (code "82") (name "unconnected-(U$3-PadB1)") (class "Default")
      (node (ref "U$3") (pin "B1") (pinfunction "B1_B1") (pintype "bidirectional"))
    )
    (net (code "83") (name "unconnected-(U$3-PadB2)") (class "Default")
      (node (ref "U$3") (pin "B2") (pinfunction "B2_B2") (pintype "bidirectional"))
    )
    (net (code "84") (name "unconnected-(U$5-BAT-PadP$BAT)") (class "Default")
      (node (ref "U$5") (pin "P$BAT") (pinfunction "BAT_P$BAT") (pintype "bidirectional"))
    )
    (net (code "85") (name "unconnected-(U$7-Pad4Y)") (class "Default")
      (node (ref "U$7") (pin "4Y") (pinfunction "4Y_4Y") (pintype "output"))
    )
    (net (code "86") (name "unconnected-(U$7-Pad5Y)") (class "Default")
      (node (ref "U$7") (pin "5Y") (pinfunction "5Y_5Y") (pintype "output"))
    )
  )
)
